# baum.net
KiCad netlist of a schematic drawn in EAGLE
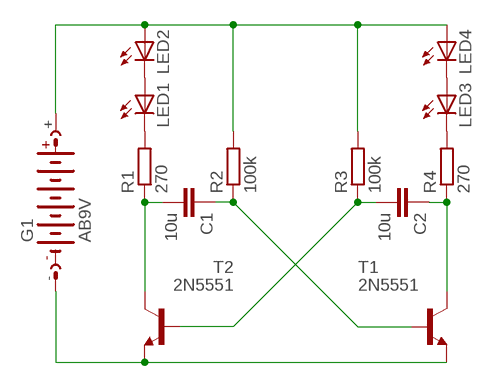
[diagram p0: schematic, sheet 1]

(export (version "E")
  (design (tool "Eeschema 10.0.6"))
  (components
    (comp (ref "C1")
      (value "10u")
      (footprint "eagle-import:C050-025X075")
      (libsource (lib "eagle-import") (part "C-EU050-025X075"))
    )
    (comp (ref "C2")
      (value "10u")
      (footprint "eagle-import:C050-025X075")
      (libsource (lib "eagle-import") (part "C-EU050-025X075"))
    )
    (comp (ref "G1")
      (value "AB9V")
      (footprint "eagle-import:AB9V")
      (libsource (lib "eagle-import") (part "AB9V"))
    )
    (comp (ref "LED1")
      (value "LED3MM")
      (footprint "eagle-import:LED3MM")
      (libsource (lib "eagle-import") (part "LED3MM"))
    )
    (comp (ref "LED2")
      (value "LED3MM")
      (footprint "eagle-import:LED3MM")
      (libsource (lib "eagle-import") (part "LED3MM"))
    )
    (comp (ref "LED3")
      (value "LED3MM")
      (footprint "eagle-import:LED3MM")
      (libsource (lib "eagle-import") (part "LED3MM"))
    )
    (comp (ref "LED4")
      (value "LED3MM")
      (footprint "eagle-import:LED3MM")
      (libsource (lib "eagle-import") (part "LED3MM"))
    )
    (comp (ref "R1")
      (value "270")
      (footprint "eagle-import:0207_10")
      (libsource (lib "eagle-import") (part "R-EU_0207/10"))
    )
    (comp (ref "R2")
      (value "100k")
      (footprint "eagle-import:0207_10")
      (libsource (lib "eagle-import") (part "R-EU_0207/10"))
    )
    (comp (ref "R3")
      (value "100k")
      (footprint "eagle-import:0207_10")
      (libsource (lib "eagle-import") (part "R-EU_0207/10"))
    )
    (comp (ref "R4")
      (value "270")
      (footprint "eagle-import:0207_10")
      (libsource (lib "eagle-import") (part "R-EU_0207/10"))
    )
    (comp (ref "T1")
      (value "2N5551")
      (footprint "eagle-import:TO92-CBE")
      (libsource (lib "eagle-import") (part "-NPN-TO92-CBE2N5551"))
    )
    (comp (ref "T2")
      (value "2N5551")
      (footprint "eagle-import:TO92-CBE")
      (libsource (lib "eagle-import") (part "-NPN-TO92-CBE2N5551"))
    )
  )
  (nets
    (net (code "1") (name "Net-(C1-Pad1)") (class "Default")
      (node (ref "C1") (pin "1") (pinfunction "1_1") (pintype "passive"))
      (node (ref "R2") (pin "1") (pinfunction "1_1") (pintype "passive"))
      (node (ref "T1") (pin "B") (pinfunction "B_B") (pintype "passive"))
    )
    (net (code "2") (name "Net-(C1-Pad2)") (class "Default")
      (node (ref "C1") (pin "2") (pinfunction "2_2") (pintype "passive"))
      (node (ref "R1") (pin "1") (pinfunction "1_1") (pintype "passive"))
      (node (ref "T2") (pin "C") (pinfunction "C_C") (pintype "passive"))
    )
    (net (code "3") (name "Net-(C2-Pad1)") (class "Default")
      (node (ref "C2") (pin "1") (pinfunction "1_1") (pintype "passive"))
      (node (ref "R4") (pin "1") (pinfunction "1_1") (pintype "passive"))
      (node (ref "T1") (pin "C") (pinfunction "C_C") (pintype "passive"))
    )
    (net (code "4") (name "Net-(C2-Pad2)") (class "Default")
      (node (ref "C2") (pin "2") (pinfunction "2_2") (pintype "passive"))
      (node (ref "R3") (pin "1") (pinfunction "1_1") (pintype "passive"))
      (node (ref "T2") (pin "B") (pinfunction "B_B") (pintype "passive"))
    )
    (net (code "5") (name "Net-(G1-Pad+)") (class "Default")
      (node (ref "G1") (pin "+") (pinfunction "+_+") (pintype "passive"))
      (node (ref "LED2") (pin "A") (pinfunction "A_A") (pintype "passive"))
      (node (ref "LED4") (pin "A") (pinfunction "A_A") (pintype "passive"))
      (node (ref "R2") (pin "2") (pinfunction "2_2") (pintype "passive"))
      (node (ref "R3") (pin "2") (pinfunction "2_2") (pintype "passive"))
    )
    (net (code "6") (name "Net-(G1-Pad-)") (class "Default")
      (node (ref "G1") (pin "-") (pinfunction "-_-") (pintype "passive"))
      (node (ref "T1") (pin "E") (pinfunction "E_E") (pintype "passive"))
      (node (ref "T2") (pin "E") (pinfunction "E_E") (pintype "passive"))
    )
    (net (code "7") (name "Net-(LED1-C)") (class "Default")
      (node (ref "LED1") (pin "K") (pinfunction "C_K") (pintype "passive"))
      (node (ref "R1") (pin "2") (pinfunction "2_2") (pintype "passive"))
    )
    (net (code "8") (name "Net-(LED2-C)") (class "Default")
      (node (ref "LED1") (pin "A") (pinfunction "A_A") (pintype "passive"))
      (node (ref "LED2") (pin "K") (pinfunction "C_K") (pintype "passive"))
    )
    (net (code "9") (name "Net-(LED3-C)") (class "Default")
      (node (ref "LED3") (pin "K") (pinfunction "C_K") (pintype "passive"))
      (node (ref "R4") (pin "2") (pinfunction "2_2") (pintype "passive"))
    )
    (net (code "10") (name "Net-(LED4-C)") (class "Default")
      (node (ref "LED3") (pin "A") (pinfunction "A_A") (pintype "passive"))
      (node (ref "LED4") (pin "K") (pinfunction "C_K") (pintype "passive"))
    )
  )
)
